# SCH.net
KiCad netlist of a schematic drawn in EasyEDA
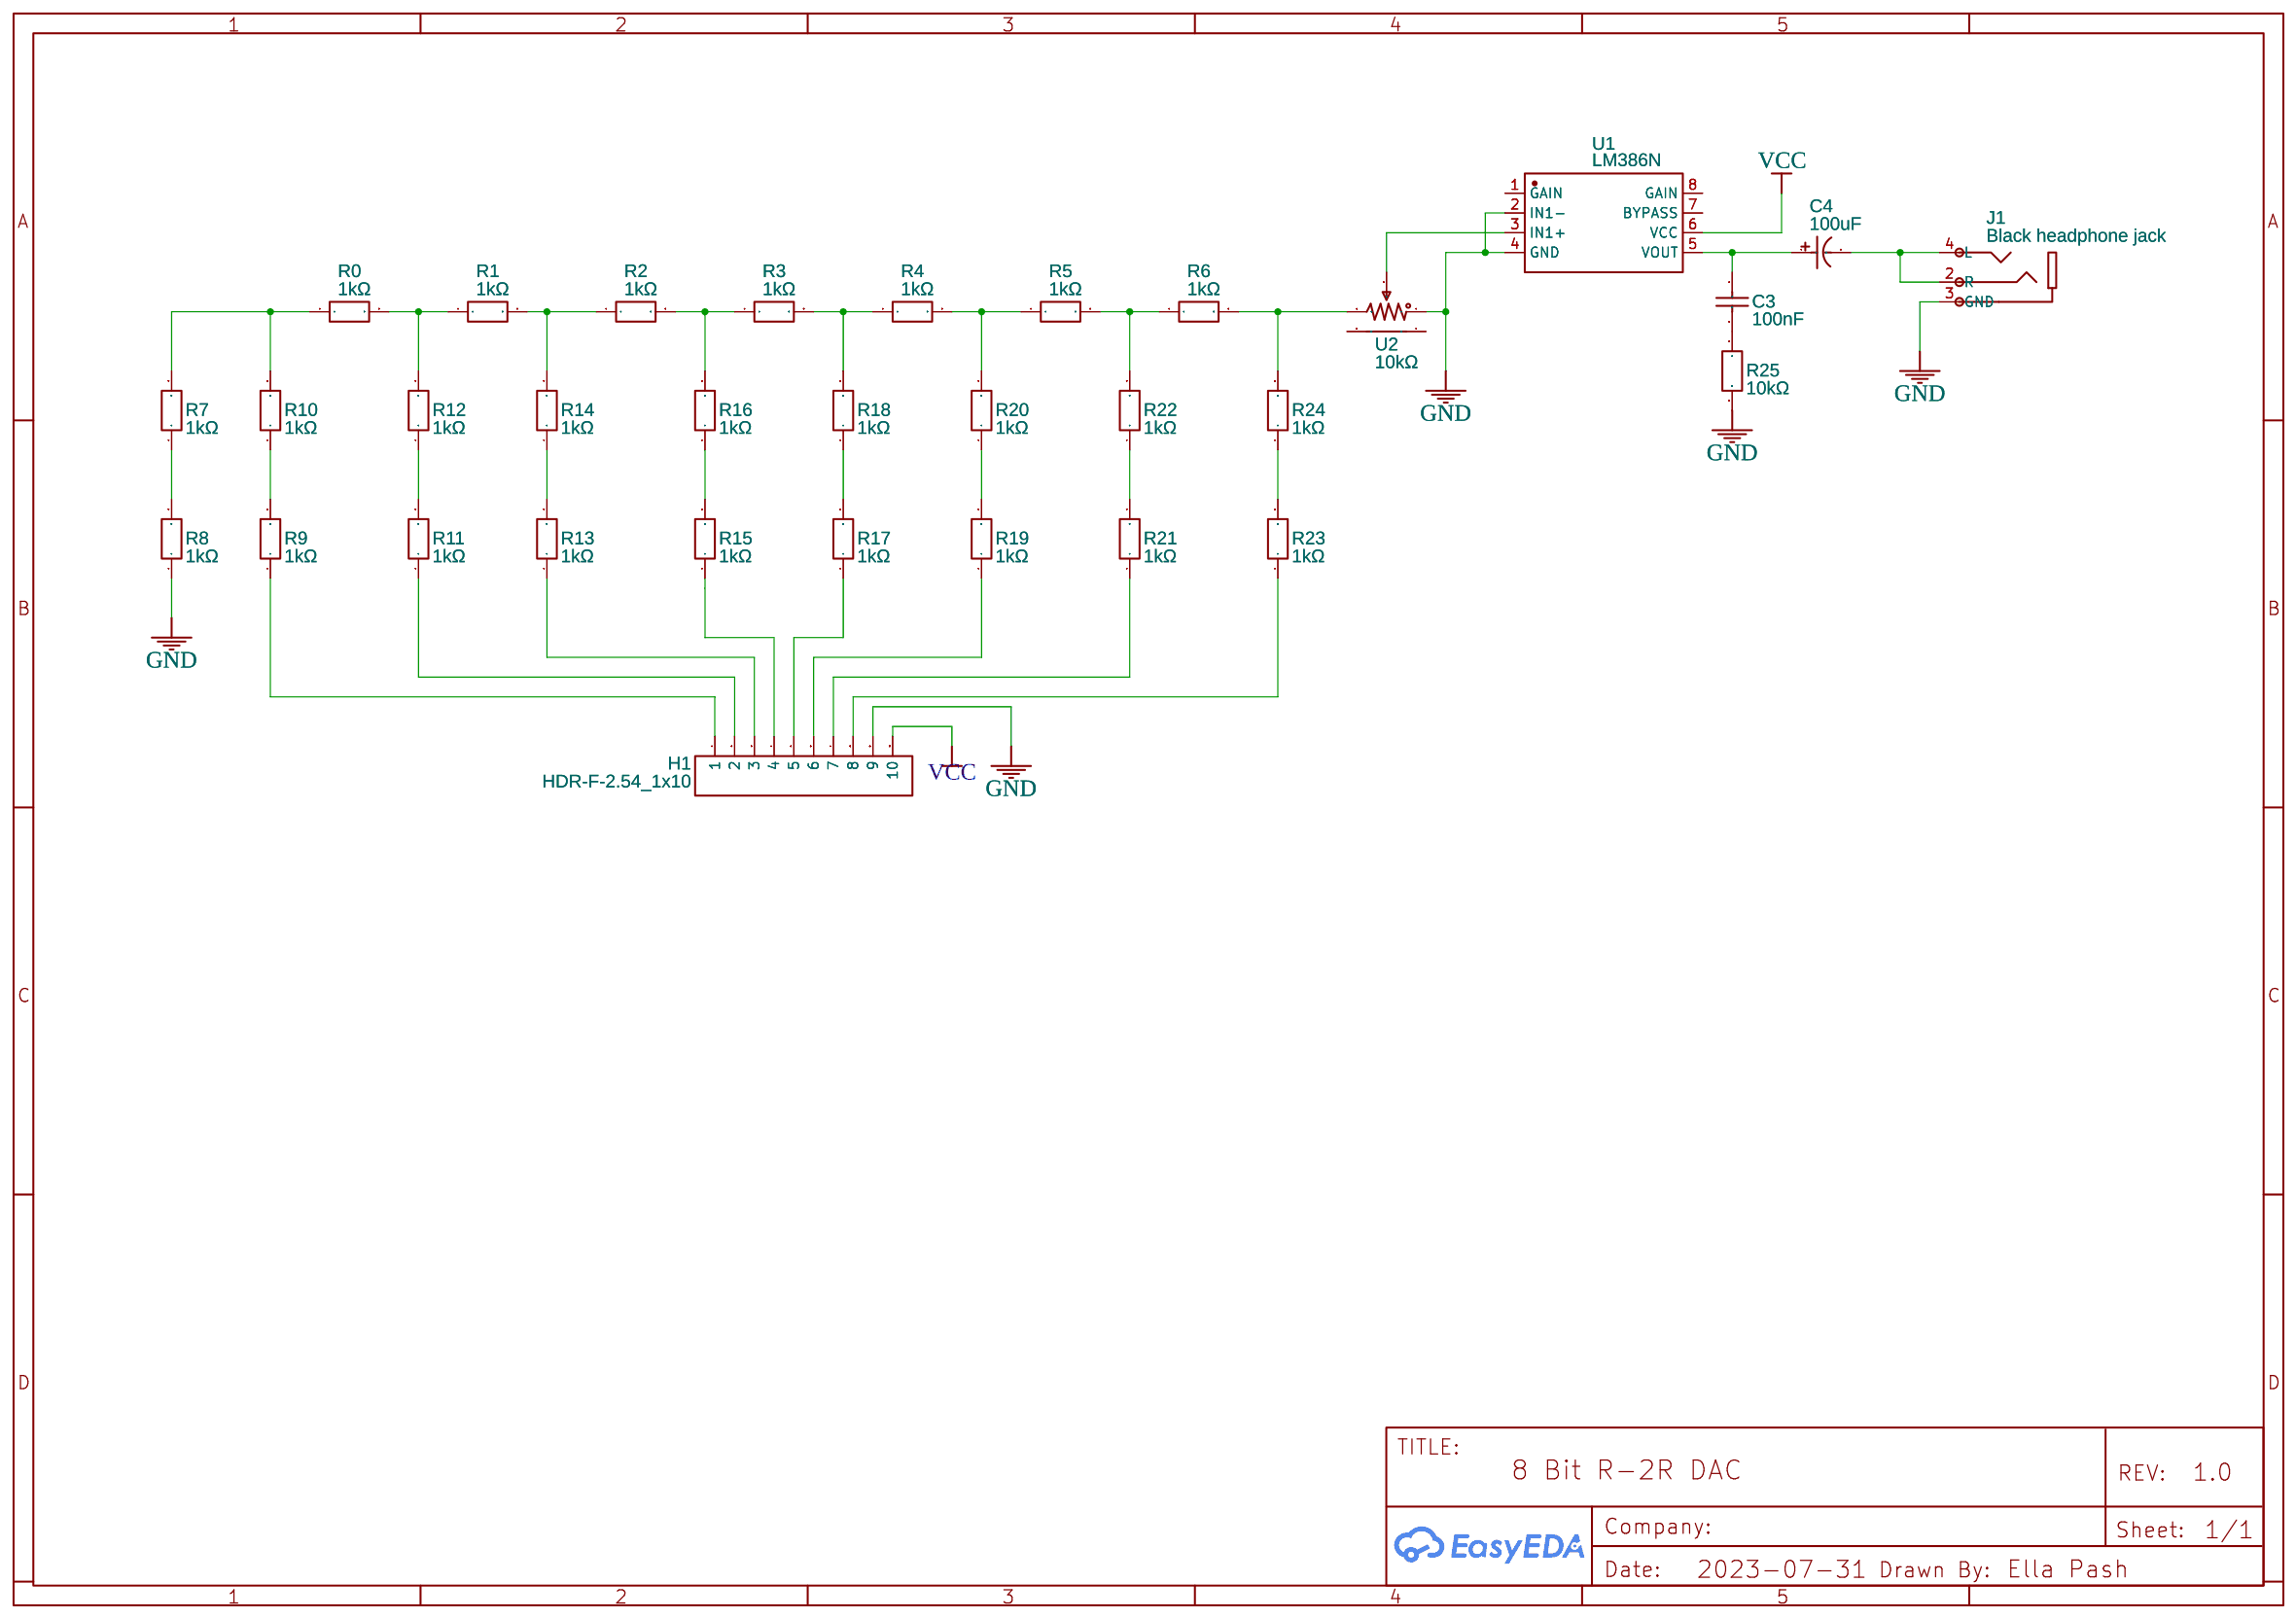
[diagram p0: schematic sheet]

(export (version "E")
  (design (tool "Eeschema 10.0.6"))
  (components
    (comp (ref "C3")
      (value "100nF")
      (fields (field (name "Manufacturer Part") "K104K20X7RH53H5") (field (name "Manufacturer") "VISHAY(威世)"))
      (libsource (lib "") (part "K104K20X7RH53H5"))
    )
    (comp (ref "C4")
      (value "100uF")
      (fields
        (field (name "Manufacturer Part") "KM107M025D11RR0VH2FP0")
        (field (name "Manufacturer") "CX(承兴)")
      )
      (libsource (lib "") (part "100uF 25V 5*11"))
    )
    (comp (ref "H1") (value "HDR-F-2.54_1x10") (libsource (lib "") (part "HDR-F-2.54_1x10")))
    (comp (ref "J1")
      (value "Black headphone jack")
      (fields (field (name "Manufacturer Part") "320B直插") (field (name "Manufacturer") "BOOMELE(博穆精密)"))
      (libsource (lib "") (part "Black headphone jack"))
    )
    (comp (ref "R0")
      (value "1kΩ")
      (fields
        (field (name "Manufacturer Part") "MF1/4W-1KΩ±1%T52")
        (field (name "Manufacturer") "Huaxing Mechanical-Elec.")
      )
      (libsource (lib "") (part "MF1/4W-1KΩ±1%T52_1"))
    )
    (comp (ref "R1")
      (value "1kΩ")
      (fields
        (field (name "Manufacturer Part") "MF1/4W-1KΩ±1%T52")
        (field (name "Manufacturer") "Huaxing Mechanical-Elec.")
      )
      (libsource (lib "") (part "MF1/4W-1KΩ±1%T52_1"))
    )
    (comp (ref "R2")
      (value "1kΩ")
      (fields
        (field (name "Manufacturer Part") "MF1/4W-1KΩ±1%T52")
        (field (name "Manufacturer") "Huaxing Mechanical-Elec.")
      )
      (libsource (lib "") (part "MF1/4W-1KΩ±1%T52_1"))
    )
    (comp (ref "R3")
      (value "1kΩ")
      (fields
        (field (name "Manufacturer Part") "MF1/4W-1KΩ±1%T52")
        (field (name "Manufacturer") "Huaxing Mechanical-Elec.")
      )
      (libsource (lib "") (part "MF1/4W-1KΩ±1%T52_1"))
    )
    (comp (ref "R4")
      (value "1kΩ")
      (fields
        (field (name "Manufacturer Part") "MF1/4W-1KΩ±1%T52")
        (field (name "Manufacturer") "Huaxing Mechanical-Elec.")
      )
      (libsource (lib "") (part "MF1/4W-1KΩ±1%T52_1"))
    )
    (comp (ref "R5")
      (value "1kΩ")
      (fields
        (field (name "Manufacturer Part") "MF1/4W-1KΩ±1%T52")
        (field (name "Manufacturer") "Huaxing Mechanical-Elec.")
      )
      (libsource (lib "") (part "MF1/4W-1KΩ±1%T52_1"))
    )
    (comp (ref "R6")
      (value "1kΩ")
      (fields
        (field (name "Manufacturer Part") "MF1/4W-1KΩ±1%T52")
        (field (name "Manufacturer") "Huaxing Mechanical-Elec.")
      )
      (libsource (lib "") (part "MF1/4W-1KΩ±1%T52_1"))
    )
    (comp (ref "R7")
      (value "1kΩ")
      (fields
        (field (name "Manufacturer Part") "MF1/4W-1KΩ±1%T52")
        (field (name "Manufacturer") "Huaxing Mechanical-Elec.")
      )
      (libsource (lib "") (part "MF1/4W-1KΩ±1%T52"))
    )
    (comp (ref "R8")
      (value "1kΩ")
      (fields
        (field (name "Manufacturer Part") "MF1/4W-1KΩ±1%T52")
        (field (name "Manufacturer") "Huaxing Mechanical-Elec.")
      )
      (libsource (lib "") (part "MF1/4W-1KΩ±1%T52"))
    )
    (comp (ref "R9")
      (value "1kΩ")
      (fields
        (field (name "Manufacturer Part") "MF1/4W-1KΩ±1%T52")
        (field (name "Manufacturer") "Huaxing Mechanical-Elec.")
      )
      (libsource (lib "") (part "MF1/4W-1KΩ±1%T52"))
    )
    (comp (ref "R10")
      (value "1kΩ")
      (fields
        (field (name "Manufacturer Part") "MF1/4W-1KΩ±1%T52")
        (field (name "Manufacturer") "Huaxing Mechanical-Elec.")
      )
      (libsource (lib "") (part "MF1/4W-1KΩ±1%T52"))
    )
    (comp (ref "R11")
      (value "1kΩ")
      (fields
        (field (name "Manufacturer Part") "MF1/4W-1KΩ±1%T52")
        (field (name "Manufacturer") "Huaxing Mechanical-Elec.")
      )
      (libsource (lib "") (part "MF1/4W-1KΩ±1%T52"))
    )
    (comp (ref "R12")
      (value "1kΩ")
      (fields
        (field (name "Manufacturer Part") "MF1/4W-1KΩ±1%T52")
        (field (name "Manufacturer") "Huaxing Mechanical-Elec.")
      )
      (libsource (lib "") (part "MF1/4W-1KΩ±1%T52"))
    )
    (comp (ref "R13")
      (value "1kΩ")
      (fields
        (field (name "Manufacturer Part") "MF1/4W-1KΩ±1%T52")
        (field (name "Manufacturer") "Huaxing Mechanical-Elec.")
      )
      (libsource (lib "") (part "MF1/4W-1KΩ±1%T52"))
    )
    (comp (ref "R14")
      (value "1kΩ")
      (fields
        (field (name "Manufacturer Part") "MF1/4W-1KΩ±1%T52")
        (field (name "Manufacturer") "Huaxing Mechanical-Elec.")
      )
      (libsource (lib "") (part "MF1/4W-1KΩ±1%T52"))
    )
    (comp (ref "R15")
      (value "1kΩ")
      (fields
        (field (name "Manufacturer Part") "MF1/4W-1KΩ±1%T52")
        (field (name "Manufacturer") "Huaxing Mechanical-Elec.")
      )
      (libsource (lib "") (part "MF1/4W-1KΩ±1%T52"))
    )
    (comp (ref "R16")
      (value "1kΩ")
      (fields
        (field (name "Manufacturer Part") "MF1/4W-1KΩ±1%T52")
        (field (name "Manufacturer") "Huaxing Mechanical-Elec.")
      )
      (libsource (lib "") (part "MF1/4W-1KΩ±1%T52"))
    )
    (comp (ref "R17")
      (value "1kΩ")
      (fields
        (field (name "Manufacturer Part") "MF1/4W-1KΩ±1%T52")
        (field (name "Manufacturer") "Huaxing Mechanical-Elec.")
      )
      (libsource (lib "") (part "MF1/4W-1KΩ±1%T52"))
    )
    (comp (ref "R18")
      (value "1kΩ")
      (fields
        (field (name "Manufacturer Part") "MF1/4W-1KΩ±1%T52")
        (field (name "Manufacturer") "Huaxing Mechanical-Elec.")
      )
      (libsource (lib "") (part "MF1/4W-1KΩ±1%T52"))
    )
    (comp (ref "R19")
      (value "1kΩ")
      (fields
        (field (name "Manufacturer Part") "MF1/4W-1KΩ±1%T52")
        (field (name "Manufacturer") "Huaxing Mechanical-Elec.")
      )
      (libsource (lib "") (part "MF1/4W-1KΩ±1%T52"))
    )
    (comp (ref "R20")
      (value "1kΩ")
      (fields
        (field (name "Manufacturer Part") "MF1/4W-1KΩ±1%T52")
        (field (name "Manufacturer") "Huaxing Mechanical-Elec.")
      )
      (libsource (lib "") (part "MF1/4W-1KΩ±1%T52"))
    )
    (comp (ref "R21")
      (value "1kΩ")
      (fields
        (field (name "Manufacturer Part") "MF1/4W-1KΩ±1%T52")
        (field (name "Manufacturer") "Huaxing Mechanical-Elec.")
      )
      (libsource (lib "") (part "MF1/4W-1KΩ±1%T52"))
    )
    (comp (ref "R22")
      (value "1kΩ")
      (fields
        (field (name "Manufacturer Part") "MF1/4W-1KΩ±1%T52")
        (field (name "Manufacturer") "Huaxing Mechanical-Elec.")
      )
      (libsource (lib "") (part "MF1/4W-1KΩ±1%T52"))
    )
    (comp (ref "R23")
      (value "1kΩ")
      (fields
        (field (name "Manufacturer Part") "MF1/4W-1KΩ±1%T52")
        (field (name "Manufacturer") "Huaxing Mechanical-Elec.")
      )
      (libsource (lib "") (part "MF1/4W-1KΩ±1%T52"))
    )
    (comp (ref "R24")
      (value "1kΩ")
      (fields
        (field (name "Manufacturer Part") "MF1/4W-1KΩ±1%T52")
        (field (name "Manufacturer") "Huaxing Mechanical-Elec.")
      )
      (libsource (lib "") (part "MF1/4W-1KΩ±1%T52"))
    )
    (comp (ref "R25")
      (value "10kΩ")
      (fields
        (field (name "Manufacturer Part") "RD1/4W10KJT/BA1")
        (field (name "Manufacturer") "Tyohm(幸亚电阻)")
      )
      (libsource (lib "") (part "RD 1/4W 10K J T/B A1"))
    )
    (comp (ref "U1")
      (value "LM386N")
      (fields (field (name "Manufacturer") "HTC"))
      (libsource (lib "") (part "LM386N"))
    )
    (comp (ref "U2")
      (value "10kΩ")
      (fields
        (field (name "Manufacturer Part") "RK09D1130C3C")
        (field (name "Manufacturer") "ALPSALPINE(阿尔卑斯阿尔派)")
      )
      (libsource (lib "") (part "RK09D1130C3C"))
    )
  )
  (nets
    (net (code "1") (name "GND") (class "Default")
      (node (ref "H1") (pin "9") (pinfunction "9_9") (pintype "unspecified"))
      (node (ref "J1") (pin "3") (pinfunction "GND_3") (pintype "input"))
      (node (ref "R25") (pin "2") (pinfunction "2_2") (pintype "unspecified"))
      (node (ref "R8") (pin "1") (pinfunction "1_1") (pintype "unspecified"))
      (node (ref "U1") (pin "2") (pinfunction "IN1-_2") (pintype "unspecified"))
      (node (ref "U1") (pin "4") (pinfunction "GND_4") (pintype "unspecified"))
      (node (ref "U2") (pin "1") (pinfunction "1_1") (pintype "unspecified"))
    )
    (net (code "2") (name "Net-(C3-Pad2)") (class "Default")
      (node (ref "C3") (pin "2") (pinfunction "2_2") (pintype "input"))
      (node (ref "R25") (pin "1") (pinfunction "1_1") (pintype "unspecified"))
    )
    (net (code "3") (name "Net-(H1-Pad1)") (class "Default")
      (node (ref "H1") (pin "1") (pinfunction "1_1") (pintype "unspecified"))
      (node (ref "R9") (pin "1") (pinfunction "1_1") (pintype "unspecified"))
    )
    (net (code "4") (name "Net-(H1-Pad2)") (class "Default")
      (node (ref "H1") (pin "2") (pinfunction "2_2") (pintype "unspecified"))
      (node (ref "R11") (pin "1") (pinfunction "1_1") (pintype "unspecified"))
    )
    (net (code "5") (name "Net-(H1-Pad3)") (class "Default")
      (node (ref "H1") (pin "3") (pinfunction "3_3") (pintype "unspecified"))
      (node (ref "R13") (pin "1") (pinfunction "1_1") (pintype "unspecified"))
    )
    (net (code "6") (name "Net-(H1-Pad4)") (class "Default")
      (node (ref "H1") (pin "4") (pinfunction "4_4") (pintype "unspecified"))
      (node (ref "R15") (pin "1") (pinfunction "1_1") (pintype "unspecified"))
    )
    (net (code "7") (name "Net-(H1-Pad5)") (class "Default")
      (node (ref "H1") (pin "5") (pinfunction "5_5") (pintype "unspecified"))
      (node (ref "R17") (pin "1") (pinfunction "1_1") (pintype "unspecified"))
    )
    (net (code "8") (name "Net-(H1-Pad6)") (class "Default")
      (node (ref "H1") (pin "6") (pinfunction "6_6") (pintype "unspecified"))
      (node (ref "R19") (pin "1") (pinfunction "1_1") (pintype "unspecified"))
    )
    (net (code "9") (name "Net-(H1-Pad7)") (class "Default")
      (node (ref "H1") (pin "7") (pinfunction "7_7") (pintype "unspecified"))
      (node (ref "R21") (pin "1") (pinfunction "1_1") (pintype "unspecified"))
    )
    (net (code "10") (name "Net-(H1-Pad8)") (class "Default")
      (node (ref "H1") (pin "8") (pinfunction "8_8") (pintype "unspecified"))
      (node (ref "R23") (pin "1") (pinfunction "1_1") (pintype "unspecified"))
    )
    (net (code "11") (name "Net-(J1-L)") (class "Default")
      (node (ref "C4") (pin "2") (pinfunction "2_2") (pintype "input"))
      (node (ref "J1") (pin "2") (pinfunction "R_2") (pintype "input"))
      (node (ref "J1") (pin "4") (pinfunction "L_4") (pintype "input"))
    )
    (net (code "12") (name "Net-(R0-Pad1)") (class "Default")
      (node (ref "R0") (pin "1") (pinfunction "1_1") (pintype "unspecified"))
      (node (ref "R10") (pin "2") (pinfunction "2_2") (pintype "unspecified"))
      (node (ref "R7") (pin "2") (pinfunction "2_2") (pintype "unspecified"))
    )
    (net (code "13") (name "Net-(R0-Pad2)") (class "Default")
      (node (ref "R0") (pin "2") (pinfunction "2_2") (pintype "unspecified"))
      (node (ref "R1") (pin "1") (pinfunction "1_1") (pintype "unspecified"))
      (node (ref "R12") (pin "2") (pinfunction "2_2") (pintype "unspecified"))
    )
    (net (code "14") (name "Net-(R1-Pad2)") (class "Default")
      (node (ref "R1") (pin "2") (pinfunction "2_2") (pintype "unspecified"))
      (node (ref "R14") (pin "2") (pinfunction "2_2") (pintype "unspecified"))
      (node (ref "R2") (pin "1") (pinfunction "1_1") (pintype "unspecified"))
    )
    (net (code "15") (name "Net-(R7-Pad1)") (class "Default")
      (node (ref "R7") (pin "1") (pinfunction "1_1") (pintype "unspecified"))
      (node (ref "R8") (pin "2") (pinfunction "2_2") (pintype "unspecified"))
    )
    (net (code "16") (name "Net-(R10-Pad1)") (class "Default")
      (node (ref "R10") (pin "1") (pinfunction "1_1") (pintype "unspecified"))
      (node (ref "R9") (pin "2") (pinfunction "2_2") (pintype "unspecified"))
    )
    (net (code "17") (name "Net-(R11-Pad2)") (class "Default")
      (node (ref "R11") (pin "2") (pinfunction "2_2") (pintype "unspecified"))
      (node (ref "R12") (pin "1") (pinfunction "1_1") (pintype "unspecified"))
    )
    (net (code "18") (name "Net-(R13-Pad2)") (class "Default")
      (node (ref "R13") (pin "2") (pinfunction "2_2") (pintype "unspecified"))
      (node (ref "R14") (pin "1") (pinfunction "1_1") (pintype "unspecified"))
    )
    (net (code "19") (name "Net-(R15-Pad2)") (class "Default")
      (node (ref "R15") (pin "2") (pinfunction "2_2") (pintype "unspecified"))
      (node (ref "R16") (pin "1") (pinfunction "1_1") (pintype "unspecified"))
    )
    (net (code "20") (name "Net-(R16-Pad2)") (class "Default")
      (node (ref "R16") (pin "2") (pinfunction "2_2") (pintype "unspecified"))
      (node (ref "R2") (pin "2") (pinfunction "2_2") (pintype "unspecified"))
      (node (ref "R3") (pin "1") (pinfunction "1_1") (pintype "unspecified"))
    )
    (net (code "21") (name "Net-(R17-Pad2)") (class "Default")
      (node (ref "R17") (pin "2") (pinfunction "2_2") (pintype "unspecified"))
      (node (ref "R18") (pin "1") (pinfunction "1_1") (pintype "unspecified"))
    )
    (net (code "22") (name "Net-(R18-Pad2)") (class "Default")
      (node (ref "R18") (pin "2") (pinfunction "2_2") (pintype "unspecified"))
      (node (ref "R3") (pin "2") (pinfunction "2_2") (pintype "unspecified"))
      (node (ref "R4") (pin "1") (pinfunction "1_1") (pintype "unspecified"))
    )
    (net (code "23") (name "Net-(R19-Pad2)") (class "Default")
      (node (ref "R19") (pin "2") (pinfunction "2_2") (pintype "unspecified"))
      (node (ref "R20") (pin "1") (pinfunction "1_1") (pintype "unspecified"))
    )
    (net (code "24") (name "Net-(R20-Pad2)") (class "Default")
      (node (ref "R20") (pin "2") (pinfunction "2_2") (pintype "unspecified"))
      (node (ref "R4") (pin "2") (pinfunction "2_2") (pintype "unspecified"))
      (node (ref "R5") (pin "1") (pinfunction "1_1") (pintype "unspecified"))
    )
    (net (code "25") (name "Net-(R21-Pad2)") (class "Default")
      (node (ref "R21") (pin "2") (pinfunction "2_2") (pintype "unspecified"))
      (node (ref "R22") (pin "1") (pinfunction "1_1") (pintype "unspecified"))
    )
    (net (code "26") (name "Net-(R22-Pad2)") (class "Default")
      (node (ref "R22") (pin "2") (pinfunction "2_2") (pintype "unspecified"))
      (node (ref "R5") (pin "2") (pinfunction "2_2") (pintype "unspecified"))
      (node (ref "R6") (pin "1") (pinfunction "1_1") (pintype "unspecified"))
    )
    (net (code "27") (name "Net-(R23-Pad2)") (class "Default")
      (node (ref "R23") (pin "2") (pinfunction "2_2") (pintype "unspecified"))
      (node (ref "R24") (pin "1") (pinfunction "1_1") (pintype "unspecified"))
    )
    (net (code "28") (name "Net-(R24-Pad2)") (class "Default")
      (node (ref "R24") (pin "2") (pinfunction "2_2") (pintype "unspecified"))
      (node (ref "R6") (pin "2") (pinfunction "2_2") (pintype "unspecified"))
      (node (ref "U2") (pin "3") (pinfunction "3_3") (pintype "unspecified"))
    )
    (net (code "29") (name "Net-(U1-IN1+)") (class "Default")
      (node (ref "U1") (pin "3") (pinfunction "IN1+_3") (pintype "unspecified"))
      (node (ref "U2") (pin "2") (pinfunction "2_2") (pintype "unspecified"))
    )
    (net (code "30") (name "Net-(U1-VOUT)") (class "Default")
      (node (ref "C3") (pin "1") (pinfunction "1_1") (pintype "input"))
      (node (ref "C4") (pin "1") (pinfunction "1_1") (pintype "input"))
      (node (ref "U1") (pin "5") (pinfunction "VOUT_5") (pintype "unspecified"))
    )
    (net (code "31") (name "VCC") (class "Default")
      (node (ref "H1") (pin "10") (pinfunction "10_10") (pintype "unspecified"))
      (node (ref "U1") (pin "6") (pinfunction "VCC_6") (pintype "unspecified"))
    )
    (net (code "32") (name "unconnected-(U1-BYPASS-Pad7)") (class "Default")
      (node (ref "U1") (pin "7") (pinfunction "BYPASS_7") (pintype "unspecified"))
    )
    (net (code "33") (name "unconnected-(U1-GAIN-Pad1)") (class "Default")
      (node (ref "U1") (pin "1") (pinfunction "GAIN_1") (pintype "unspecified"))
    )
    (net (code "34") (name "unconnected-(U1-GAIN-Pad8)") (class "Default")
      (node (ref "U1") (pin "8") (pinfunction "GAIN_8") (pintype "unspecified"))
    )
    (net (code "35") (name "unconnected-(U2-Pad4)") (class "Default")
      (node (ref "U2") (pin "4") (pinfunction "4_4") (pintype "unspecified"))
    )
    (net (code "36") (name "unconnected-(U2-Pad5)") (class "Default")
      (node (ref "U2") (pin "5") (pinfunction "5_5") (pintype "unspecified"))
    )
  )
)
